# connectors.net
KiCad netlist of a schematic drawn in Altium Designer
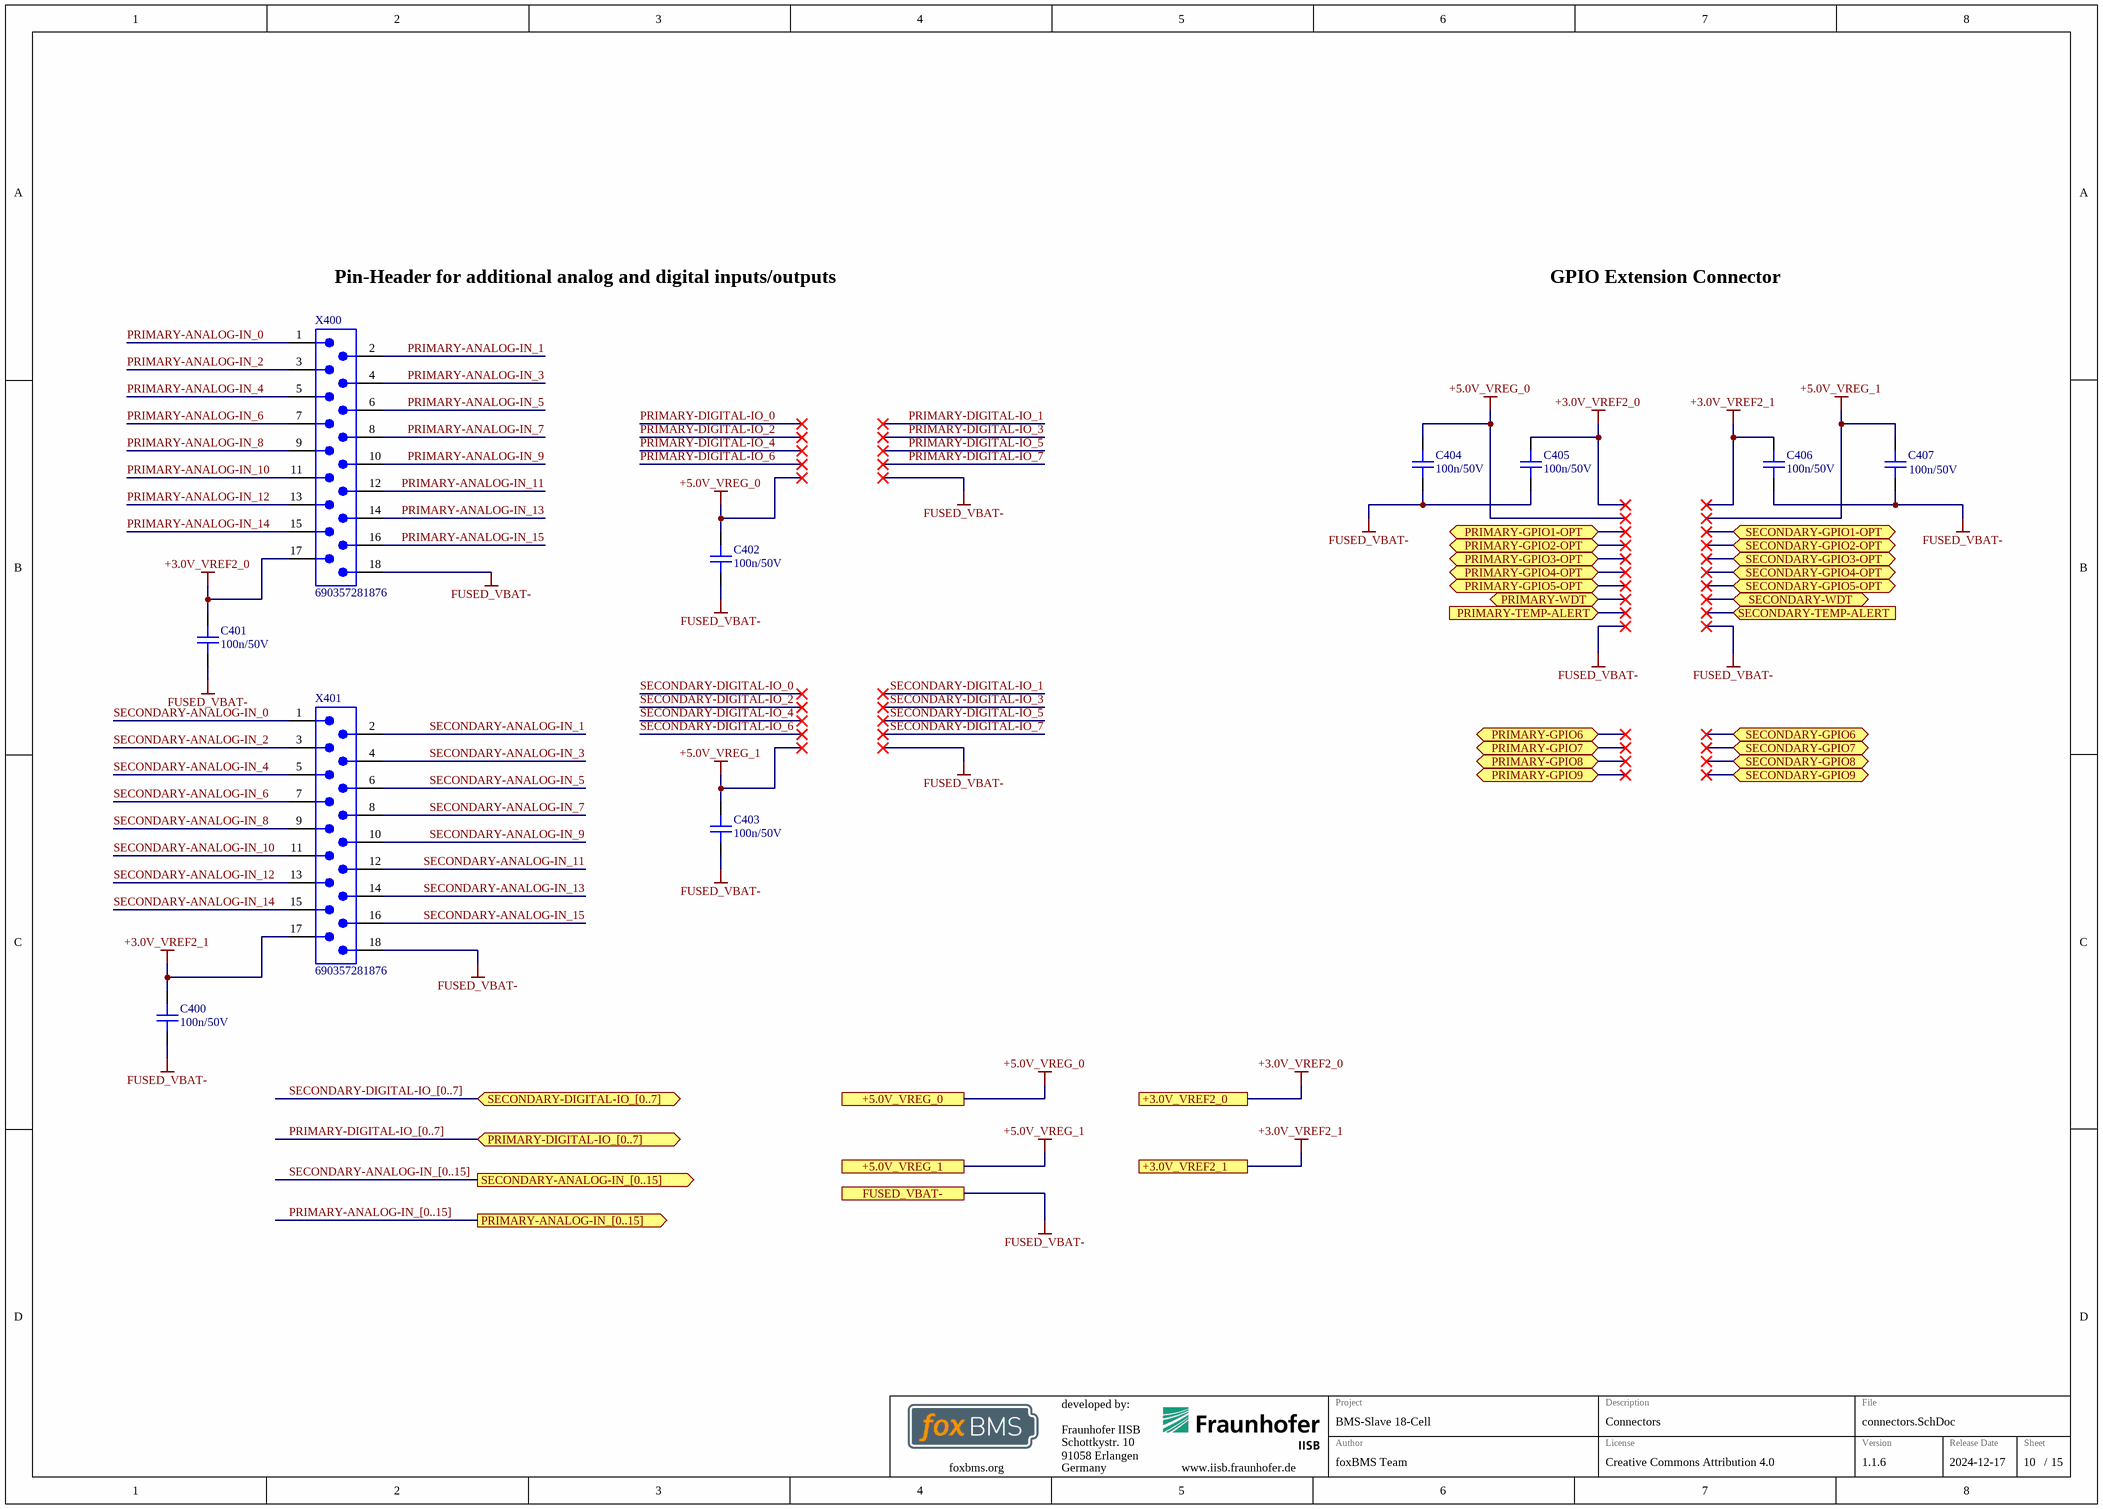
[diagram p0: connectors.SchDoc]

(export (version "E")
  (design (tool "Eeschema 10.0.6"))
  (components
    (comp (ref "C400")
      (value "100n/50V")
      (footprint "CAPC1608X08N")
      (description "MLCC")
      (fields (field (name "PART NUMBER") "gen_C_ceramic_100n_50V_X7R_0603"))
      (libsource (lib "OE750") (part "C"))
    )
    (comp (ref "C401")
      (value "100n/50V")
      (footprint "CAPC1608X08N")
      (description "MLCC")
      (fields (field (name "PART NUMBER") "gen_C_ceramic_100n_50V_X7R_0603"))
      (libsource (lib "OE750") (part "C"))
    )
    (comp (ref "C402")
      (value "100n/50V")
      (footprint "CAPC1608X08N")
      (description "MLCC")
      (fields (field (name "PART NUMBER") "gen_C_ceramic_100n_50V_X7R_0603"))
      (libsource (lib "OE750") (part "C"))
    )
    (comp (ref "C403")
      (value "100n/50V")
      (footprint "CAPC1608X08N")
      (description "MLCC")
      (fields (field (name "PART NUMBER") "gen_C_ceramic_100n_50V_X7R_0603"))
      (libsource (lib "OE750") (part "C"))
    )
    (comp (ref "C404")
      (value "100n/50V")
      (footprint "CAPC1608X08N")
      (description "MLCC")
      (fields (field (name "PART NUMBER") "gen_C_ceramic_100n_50V_X7R_0603"))
      (libsource (lib "OE750") (part "C"))
    )
    (comp (ref "C405")
      (value "100n/50V")
      (footprint "CAPC1608X08N")
      (description "MLCC")
      (fields (field (name "PART NUMBER") "gen_C_ceramic_100n_50V_X7R_0603"))
      (libsource (lib "OE750") (part "C"))
    )
    (comp (ref "C406")
      (value "100n/50V")
      (footprint "CAPC1608X08N")
      (description "MLCC")
      (fields (field (name "PART NUMBER") "gen_C_ceramic_100n_50V_X7R_0603"))
      (libsource (lib "OE750") (part "C"))
    )
    (comp (ref "C407")
      (value "100n/50V")
      (footprint "CAPC1608X08N")
      (description "MLCC")
      (fields (field (name "PART NUMBER") "gen_C_ceramic_100n_50V_X7R_0603"))
      (libsource (lib "OE750") (part "C"))
    )
    (comp (ref "X400")
      (value "690357281876")
      (footprint "690357281876")
      (libsource (lib "Altium Content Vault") (part "MM_Male_18P"))
    )
    (comp (ref "X401")
      (value "690357281876")
      (footprint "690357281876")
      (libsource (lib "Altium Content Vault") (part "MM_Male_18P"))
    )
  )
  (nets
    (net (code "1") (name "+3.0V_VREF2_0") (class "Default")
      (node (ref "C401") (pin "2") (pinfunction "2_2") (pintype "passive"))
      (node (ref "C405") (pin "2") (pinfunction "2_2") (pintype "passive"))
      (node (ref "X400") (pin "17") (pinfunction "17_17") (pintype "passive"))
    )
    (net (code "2") (name "+3.0V_VREF2_1") (class "Default")
      (node (ref "C400") (pin "2") (pinfunction "2_2") (pintype "passive"))
      (node (ref "C406") (pin "2") (pinfunction "2_2") (pintype "passive"))
      (node (ref "X401") (pin "17") (pinfunction "17_17") (pintype "passive"))
    )
    (net (code "3") (name "+5.0V_VREG_0") (class "Default")
      (node (ref "C402") (pin "2") (pinfunction "2_2") (pintype "passive"))
      (node (ref "C404") (pin "2") (pinfunction "2_2") (pintype "passive"))
    )
    (net (code "4") (name "+5.0V_VREG_1") (class "Default")
      (node (ref "C403") (pin "2") (pinfunction "2_2") (pintype "passive"))
      (node (ref "C407") (pin "2") (pinfunction "2_2") (pintype "passive"))
    )
    (net (code "5") (name "/PRIMARY-ANALOG-IN_0") (class "Default")
      (node (ref "X400") (pin "1") (pinfunction "1_1") (pintype "passive"))
    )
    (net (code "6") (name "/PRIMARY-ANALOG-IN_1") (class "Default")
      (node (ref "X400") (pin "2") (pinfunction "2_2") (pintype "passive"))
    )
    (net (code "7") (name "/PRIMARY-ANALOG-IN_2") (class "Default")
      (node (ref "X400") (pin "3") (pinfunction "3_3") (pintype "passive"))
    )
    (net (code "8") (name "/PRIMARY-ANALOG-IN_3") (class "Default")
      (node (ref "X400") (pin "4") (pinfunction "4_4") (pintype "passive"))
    )
    (net (code "9") (name "/PRIMARY-ANALOG-IN_4") (class "Default")
      (node (ref "X400") (pin "5") (pinfunction "5_5") (pintype "passive"))
    )
    (net (code "10") (name "/PRIMARY-ANALOG-IN_5") (class "Default")
      (node (ref "X400") (pin "6") (pinfunction "6_6") (pintype "passive"))
    )
    (net (code "11") (name "/PRIMARY-ANALOG-IN_6") (class "Default")
      (node (ref "X400") (pin "7") (pinfunction "7_7") (pintype "passive"))
    )
    (net (code "12") (name "/PRIMARY-ANALOG-IN_7") (class "Default")
      (node (ref "X400") (pin "8") (pinfunction "8_8") (pintype "passive"))
    )
    (net (code "13") (name "/PRIMARY-ANALOG-IN_8") (class "Default")
      (node (ref "X400") (pin "9") (pinfunction "9_9") (pintype "passive"))
    )
    (net (code "14") (name "/PRIMARY-ANALOG-IN_9") (class "Default")
      (node (ref "X400") (pin "10") (pinfunction "10_10") (pintype "passive"))
    )
    (net (code "15") (name "/PRIMARY-ANALOG-IN_10") (class "Default")
      (node (ref "X400") (pin "11") (pinfunction "11_11") (pintype "passive"))
    )
    (net (code "16") (name "/PRIMARY-ANALOG-IN_11") (class "Default")
      (node (ref "X400") (pin "12") (pinfunction "12_12") (pintype "passive"))
    )
    (net (code "17") (name "/PRIMARY-ANALOG-IN_12") (class "Default")
      (node (ref "X400") (pin "13") (pinfunction "13_13") (pintype "passive"))
    )
    (net (code "18") (name "/PRIMARY-ANALOG-IN_13") (class "Default")
      (node (ref "X400") (pin "14") (pinfunction "14_14") (pintype "passive"))
    )
    (net (code "19") (name "/PRIMARY-ANALOG-IN_14") (class "Default")
      (node (ref "X400") (pin "15") (pinfunction "15_15") (pintype "passive"))
    )
    (net (code "20") (name "/PRIMARY-ANALOG-IN_15") (class "Default")
      (node (ref "X400") (pin "16") (pinfunction "16_16") (pintype "passive"))
    )
    (net (code "42") (name "/SECONDARY-ANALOG-IN_0") (class "Default")
      (node (ref "X401") (pin "1") (pinfunction "1_1") (pintype "passive"))
    )
    (net (code "43") (name "/SECONDARY-ANALOG-IN_1") (class "Default")
      (node (ref "X401") (pin "2") (pinfunction "2_2") (pintype "passive"))
    )
    (net (code "44") (name "/SECONDARY-ANALOG-IN_2") (class "Default")
      (node (ref "X401") (pin "3") (pinfunction "3_3") (pintype "passive"))
    )
    (net (code "45") (name "/SECONDARY-ANALOG-IN_3") (class "Default")
      (node (ref "X401") (pin "4") (pinfunction "4_4") (pintype "passive"))
    )
    (net (code "46") (name "/SECONDARY-ANALOG-IN_4") (class "Default")
      (node (ref "X401") (pin "5") (pinfunction "5_5") (pintype "passive"))
    )
    (net (code "47") (name "/SECONDARY-ANALOG-IN_5") (class "Default")
      (node (ref "X401") (pin "6") (pinfunction "6_6") (pintype "passive"))
    )
    (net (code "48") (name "/SECONDARY-ANALOG-IN_6") (class "Default")
      (node (ref "X401") (pin "7") (pinfunction "7_7") (pintype "passive"))
    )
    (net (code "49") (name "/SECONDARY-ANALOG-IN_7") (class "Default")
      (node (ref "X401") (pin "8") (pinfunction "8_8") (pintype "passive"))
    )
    (net (code "50") (name "/SECONDARY-ANALOG-IN_8") (class "Default")
      (node (ref "X401") (pin "9") (pinfunction "9_9") (pintype "passive"))
    )
    (net (code "51") (name "/SECONDARY-ANALOG-IN_9") (class "Default")
      (node (ref "X401") (pin "10") (pinfunction "10_10") (pintype "passive"))
    )
    (net (code "52") (name "/SECONDARY-ANALOG-IN_10") (class "Default")
      (node (ref "X401") (pin "11") (pinfunction "11_11") (pintype "passive"))
    )
    (net (code "53") (name "/SECONDARY-ANALOG-IN_11") (class "Default")
      (node (ref "X401") (pin "12") (pinfunction "12_12") (pintype "passive"))
    )
    (net (code "54") (name "/SECONDARY-ANALOG-IN_12") (class "Default")
      (node (ref "X401") (pin "13") (pinfunction "13_13") (pintype "passive"))
    )
    (net (code "55") (name "/SECONDARY-ANALOG-IN_13") (class "Default")
      (node (ref "X401") (pin "14") (pinfunction "14_14") (pintype "passive"))
    )
    (net (code "56") (name "/SECONDARY-ANALOG-IN_14") (class "Default")
      (node (ref "X401") (pin "15") (pinfunction "15_15") (pintype "passive"))
    )
    (net (code "57") (name "/SECONDARY-ANALOG-IN_15") (class "Default")
      (node (ref "X401") (pin "16") (pinfunction "16_16") (pintype "passive"))
    )
    (net (code "79") (name "FUSED_VBAT-") (class "Default")
      (node (ref "C400") (pin "1") (pinfunction "1_1") (pintype "passive"))
      (node (ref "C401") (pin "1") (pinfunction "1_1") (pintype "passive"))
      (node (ref "C402") (pin "1") (pinfunction "1_1") (pintype "passive"))
      (node (ref "C403") (pin "1") (pinfunction "1_1") (pintype "passive"))
      (node (ref "C404") (pin "1") (pinfunction "1_1") (pintype "passive"))
      (node (ref "C405") (pin "1") (pinfunction "1_1") (pintype "passive"))
      (node (ref "C406") (pin "1") (pinfunction "1_1") (pintype "passive"))
      (node (ref "C407") (pin "1") (pinfunction "1_1") (pintype "passive"))
      (node (ref "X400") (pin "18") (pinfunction "18_18") (pintype "passive"))
      (node (ref "X401") (pin "18") (pinfunction "18_18") (pintype "passive"))
    )
  )
)
